# dd_current_sense.net
KiCad netlist of a schematic drawn in Altium Designer
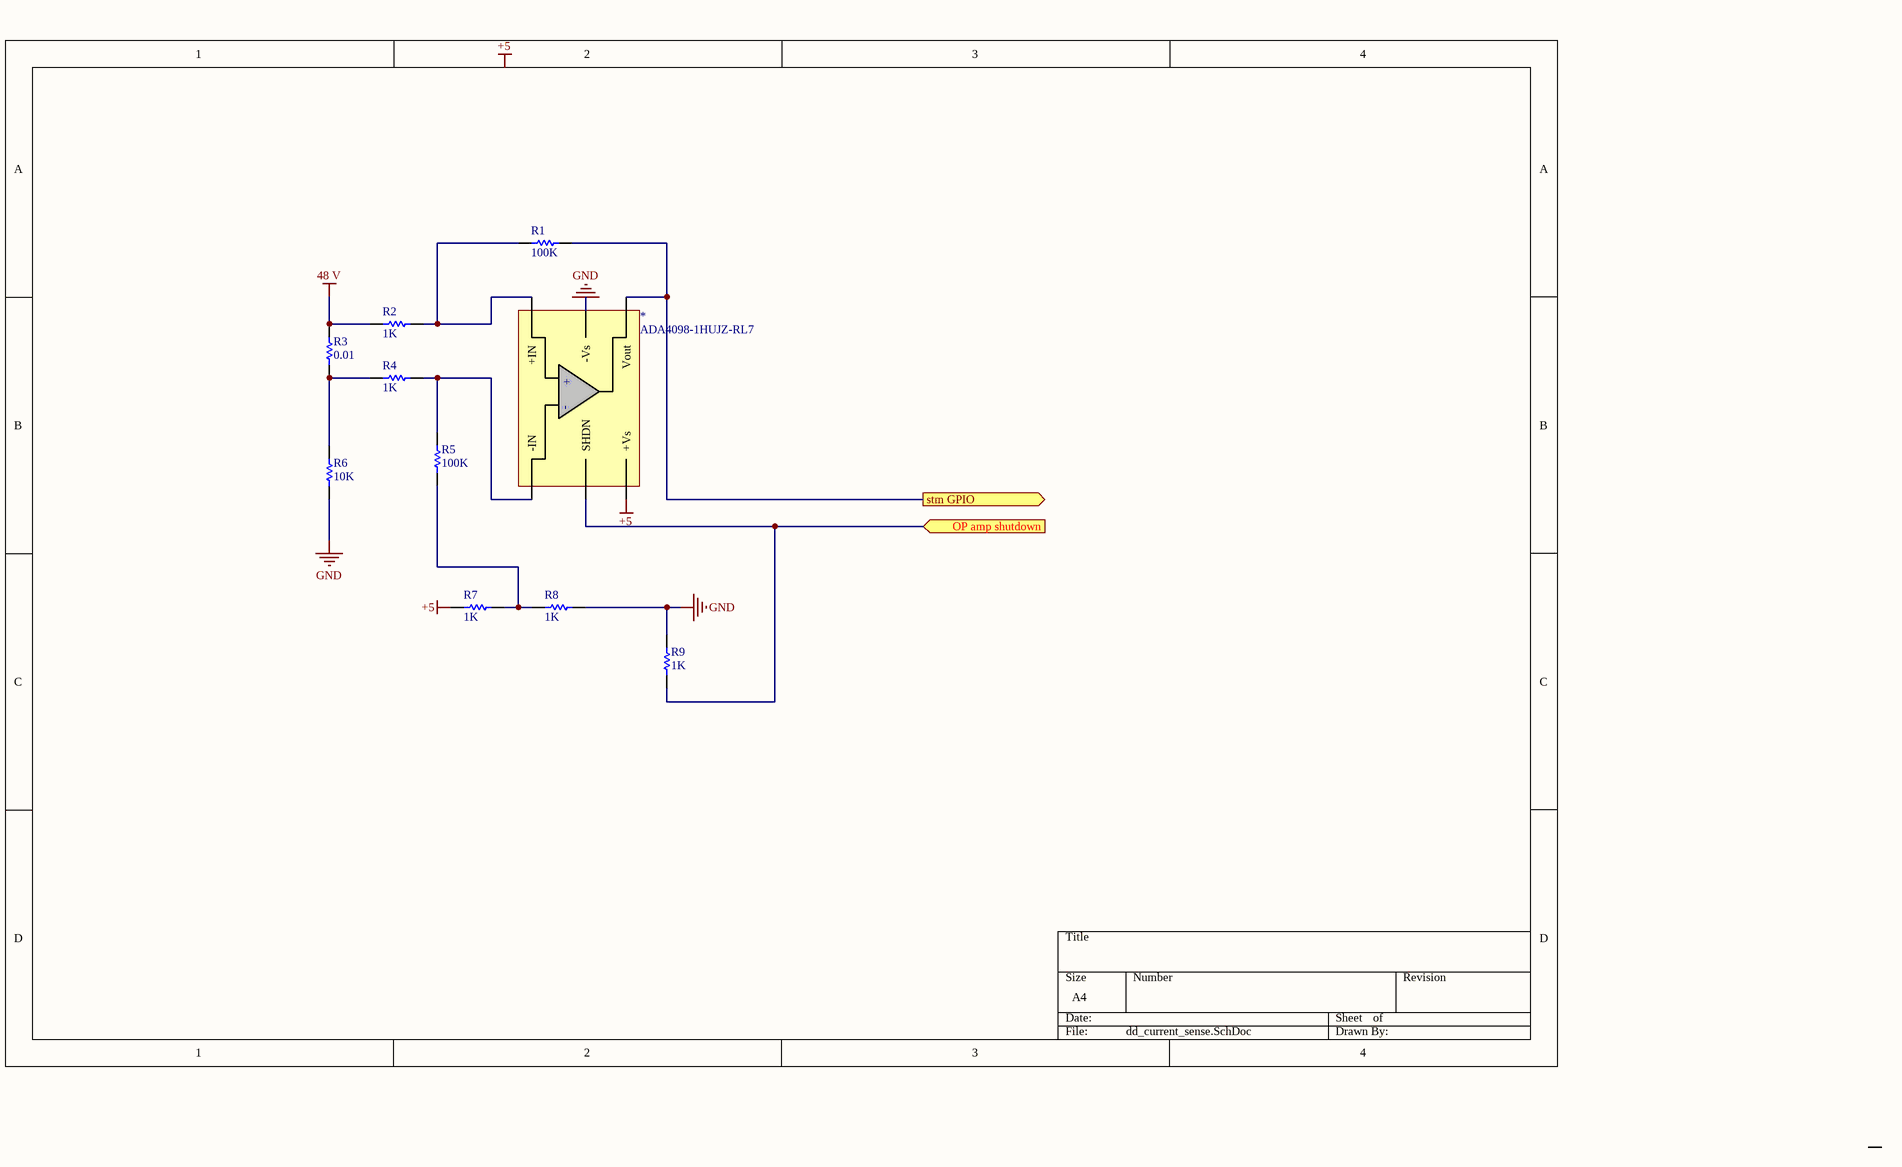
[diagram p0: dd_current_sense.SchDoc]

(export (version "E")
  (design (tool "Eeschema 10.0.6"))
  (components
    (comp (ref "*")
      (value "ADA4098-1HUJZ-RL7")
      (fields (field (name "MANUFACTURER") "Analog Devices"))
      (libsource (lib "UWRT dd_current sense") (part "ADA4098-1HUJZ-RL7"))
    )
    (comp (ref "R1")
      (value "100K")
      (description "Resistor")
      (libsource (lib "Simulation Generic Components") (part "Resistor"))
    )
    (comp (ref "R2")
      (value "1K")
      (description "Resistor")
      (libsource (lib "Simulation Generic Components") (part "Resistor"))
    )
    (comp (ref "R3")
      (value "0.01")
      (description "Resistor")
      (libsource (lib "Simulation Generic Components") (part "Resistor"))
    )
    (comp (ref "R4")
      (value "1K")
      (description "Resistor")
      (libsource (lib "Simulation Generic Components") (part "Resistor"))
    )
    (comp (ref "R5")
      (value "100K")
      (description "Resistor")
      (libsource (lib "Simulation Generic Components") (part "Resistor"))
    )
    (comp (ref "R6")
      (value "10K")
      (description "Resistor")
      (libsource (lib "Simulation Generic Components") (part "Resistor"))
    )
    (comp (ref "R7")
      (value "1K")
      (description "Resistor")
      (libsource (lib "Simulation Generic Components") (part "Resistor"))
    )
    (comp (ref "R8")
      (value "1K")
      (description "Resistor")
      (libsource (lib "Simulation Generic Components") (part "Resistor"))
    )
    (comp (ref "R9")
      (value "1K")
      (description "Resistor")
      (libsource (lib "Simulation Generic Components") (part "Resistor"))
    )
  )
  (nets
    (net (code "1") (name "+5") (class "Default")
      (node (ref "*") (pin "45") (pinfunction "+Vs_45") (pintype "passive"))
      (node (ref "R7") (pin "1") (pinfunction "1_1") (pintype "passive"))
    )
    (net (code "2") (name "/OP amp shutdown") (class "Default")
      (node (ref "*") (pin "44") (pinfunction "SHDN_44") (pintype "passive"))
      (node (ref "R9") (pin "2") (pinfunction "2_2") (pintype "passive"))
    )
    (net (code "3") (name "/stm GPIO") (class "Default")
      (node (ref "*") (pin "40") (pinfunction "Vout_40") (pintype "passive"))
      (node (ref "R1") (pin "2") (pinfunction "2_2") (pintype "passive"))
    )
    (net (code "4") (name "48 V") (class "Default")
      (node (ref "R2") (pin "1") (pinfunction "1_1") (pintype "passive"))
      (node (ref "R3") (pin "2") (pinfunction "2_2") (pintype "passive"))
    )
    (net (code "5") (name "GND") (class "Default")
      (node (ref "*") (pin "41") (pinfunction "-Vs_41") (pintype "passive"))
      (node (ref "R6") (pin "1") (pinfunction "1_1") (pintype "passive"))
      (node (ref "R8") (pin "2") (pinfunction "2_2") (pintype "passive"))
      (node (ref "R9") (pin "1") (pinfunction "1_1") (pintype "passive"))
    )
    (net (code "6") (name "Net-(*-+IN)") (class "Default")
      (node (ref "*") (pin "42") (pinfunction "+IN_42") (pintype "passive"))
      (node (ref "R1") (pin "1") (pinfunction "1_1") (pintype "passive"))
      (node (ref "R2") (pin "2") (pinfunction "2_2") (pintype "passive"))
    )
    (net (code "7") (name "Net-(*--IN)") (class "Default")
      (node (ref "*") (pin "43") (pinfunction "-IN_43") (pintype "passive"))
      (node (ref "R4") (pin "2") (pinfunction "2_2") (pintype "passive"))
      (node (ref "R5") (pin "1") (pinfunction "1_1") (pintype "passive"))
    )
    (net (code "8") (name "Net-(R3-Pad1)") (class "Default")
      (node (ref "R3") (pin "1") (pinfunction "1_1") (pintype "passive"))
      (node (ref "R4") (pin "1") (pinfunction "1_1") (pintype "passive"))
      (node (ref "R6") (pin "2") (pinfunction "2_2") (pintype "passive"))
    )
    (net (code "9") (name "Net-(R5-Pad2)") (class "Default")
      (node (ref "R5") (pin "2") (pinfunction "2_2") (pintype "passive"))
      (node (ref "R7") (pin "2") (pinfunction "2_2") (pintype "passive"))
      (node (ref "R8") (pin "1") (pinfunction "1_1") (pintype "passive"))
    )
  )
)
